# UI_breakout_slim.net
KiCad netlist of a schematic drawn in EAGLE
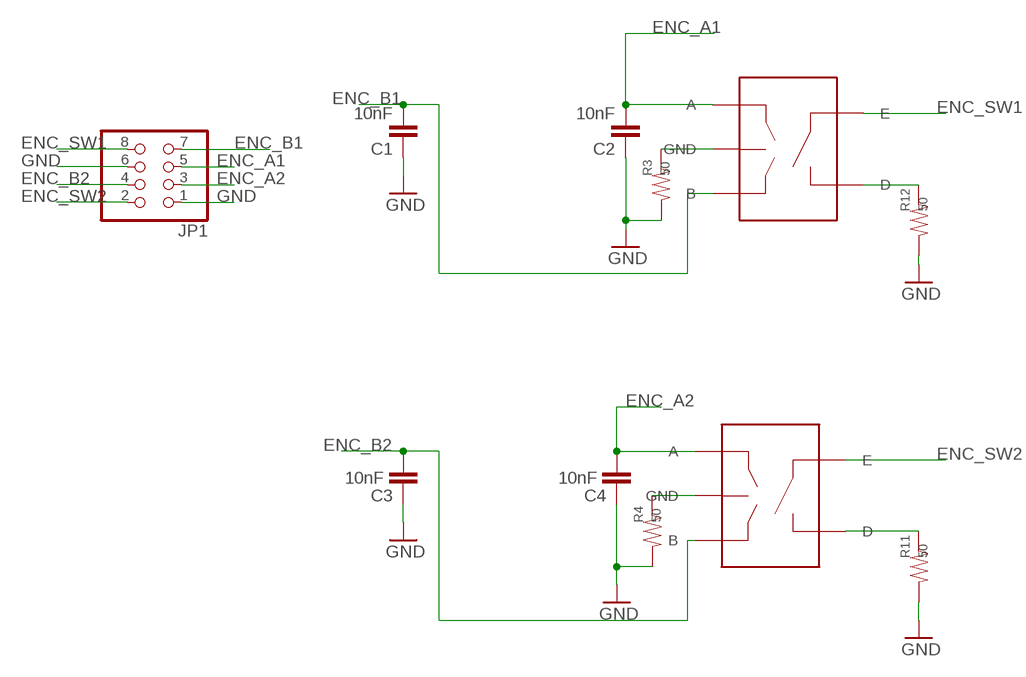
[diagram p0: schematic, sheet 1]

(export (version "E")
  (design (tool "Eeschema 10.0.6"))
  (components
    (comp (ref "C1")
      (value "10nF")
      (footprint "eagle-import:C0603")
      (libsource (lib "eagle-import") (part "C-EUC0603"))
    )
    (comp (ref "C2")
      (value "10nF")
      (footprint "eagle-import:C0603")
      (libsource (lib "eagle-import") (part "C-EUC0603"))
    )
    (comp (ref "C3")
      (value "10nF")
      (footprint "eagle-import:C0603")
      (libsource (lib "eagle-import") (part "C-EUC0603"))
    )
    (comp (ref "C4")
      (value "10nF")
      (footprint "eagle-import:C0603")
      (libsource (lib "eagle-import") (part "C-EUC0603"))
    )
    (comp (ref "ENC1")
      (value "PEC09")
      (footprint "eagle-import:PEC092320FS")
      (libsource (lib "eagle-import") (part "PEC09"))
    )
    (comp (ref "ENC2")
      (value "PEC09")
      (footprint "eagle-import:PEC092320FS")
      (libsource (lib "eagle-import") (part "PEC09"))
    )
    (comp (ref "JP1")
      (value "PINHD-2X4-SHROUD")
      (footprint "eagle-import:ML08")
      (libsource (lib "eagle-import") (part "PINHD-2X4-SHROUD"))
    )
    (comp (ref "R3")
      (value "50")
      (footprint "eagle-import:0603")
      (libsource (lib "eagle-import") (part "RES0603"))
    )
    (comp (ref "R4")
      (value "50")
      (footprint "eagle-import:0603")
      (libsource (lib "eagle-import") (part "RES0603"))
    )
    (comp (ref "R11")
      (value "50")
      (footprint "eagle-import:0603")
      (libsource (lib "eagle-import") (part "RES0603"))
    )
    (comp (ref "R12")
      (value "50")
      (footprint "eagle-import:0603")
      (libsource (lib "eagle-import") (part "RES0603"))
    )
  )
  (nets
    (net (code "1") (name "/ENC_A1") (class "Default")
      (node (ref "C2") (pin "2") (pinfunction "2_2") (pintype "passive"))
      (node (ref "ENC1") (pin "A") (pinfunction "A_A") (pintype "bidirectional"))
      (node (ref "JP1") (pin "5") (pinfunction "5_5") (pintype "passive"))
    )
    (net (code "2") (name "/ENC_A2") (class "Default")
      (node (ref "C4") (pin "2") (pinfunction "2_2") (pintype "passive"))
      (node (ref "ENC2") (pin "A") (pinfunction "A_A") (pintype "bidirectional"))
      (node (ref "JP1") (pin "3") (pinfunction "3_3") (pintype "passive"))
    )
    (net (code "3") (name "/ENC_B1") (class "Default")
      (node (ref "C1") (pin "2") (pinfunction "2_2") (pintype "passive"))
      (node (ref "ENC1") (pin "B") (pinfunction "B_B") (pintype "bidirectional"))
      (node (ref "JP1") (pin "7") (pinfunction "7_7") (pintype "passive"))
    )
    (net (code "4") (name "/ENC_B2") (class "Default")
      (node (ref "C3") (pin "2") (pinfunction "2_2") (pintype "passive"))
      (node (ref "ENC2") (pin "B") (pinfunction "B_B") (pintype "bidirectional"))
      (node (ref "JP1") (pin "4") (pinfunction "4_4") (pintype "passive"))
    )
    (net (code "5") (name "/ENC_SW1") (class "Default")
      (node (ref "ENC1") (pin "E") (pinfunction "E_E") (pintype "bidirectional"))
      (node (ref "JP1") (pin "8") (pinfunction "8_8") (pintype "passive"))
    )
    (net (code "6") (name "/ENC_SW2") (class "Default")
      (node (ref "ENC2") (pin "E") (pinfunction "E_E") (pintype "bidirectional"))
      (node (ref "JP1") (pin "2") (pinfunction "2_2") (pintype "passive"))
    )
    (net (code "7") (name "GND") (class "Default")
      (node (ref "C1") (pin "1") (pinfunction "1_1") (pintype "passive"))
      (node (ref "C2") (pin "1") (pinfunction "1_1") (pintype "passive"))
      (node (ref "C3") (pin "1") (pinfunction "1_1") (pintype "passive"))
      (node (ref "C4") (pin "1") (pinfunction "1_1") (pintype "passive"))
      (node (ref "JP1") (pin "1") (pinfunction "1_1") (pintype "passive"))
      (node (ref "JP1") (pin "6") (pinfunction "6_6") (pintype "passive"))
      (node (ref "R11") (pin "1") (pinfunction "P$1_1") (pintype "passive"))
      (node (ref "R12") (pin "1") (pinfunction "P$1_1") (pintype "passive"))
      (node (ref "R3") (pin "1") (pinfunction "P$1_1") (pintype "passive"))
      (node (ref "R4") (pin "1") (pinfunction "P$1_1") (pintype "passive"))
    )
    (net (code "8") (name "Net-(ENC1-GND)") (class "Default")
      (node (ref "ENC1") (pin "C") (pinfunction "GND_C") (pintype "bidirectional"))
      (node (ref "R3") (pin "2") (pinfunction "P$2_2") (pintype "passive"))
    )
    (net (code "9") (name "Net-(ENC2-GND)") (class "Default")
      (node (ref "ENC2") (pin "C") (pinfunction "GND_C") (pintype "bidirectional"))
      (node (ref "R4") (pin "2") (pinfunction "P$2_2") (pintype "passive"))
    )
    (net (code "10") (name "Net-(R11-P$2)") (class "Default")
      (node (ref "ENC2") (pin "D") (pinfunction "D_D") (pintype "bidirectional"))
      (node (ref "R11") (pin "2") (pinfunction "P$2_2") (pintype "passive"))
    )
    (net (code "11") (name "Net-(R12-P$2)") (class "Default")
      (node (ref "ENC1") (pin "D") (pinfunction "D_D") (pintype "bidirectional"))
      (node (ref "R12") (pin "2") (pinfunction "P$2_2") (pintype "passive"))
    )
  )
)
